# qfp160_socket_new.net
KiCad netlist of a schematic drawn in EAGLE
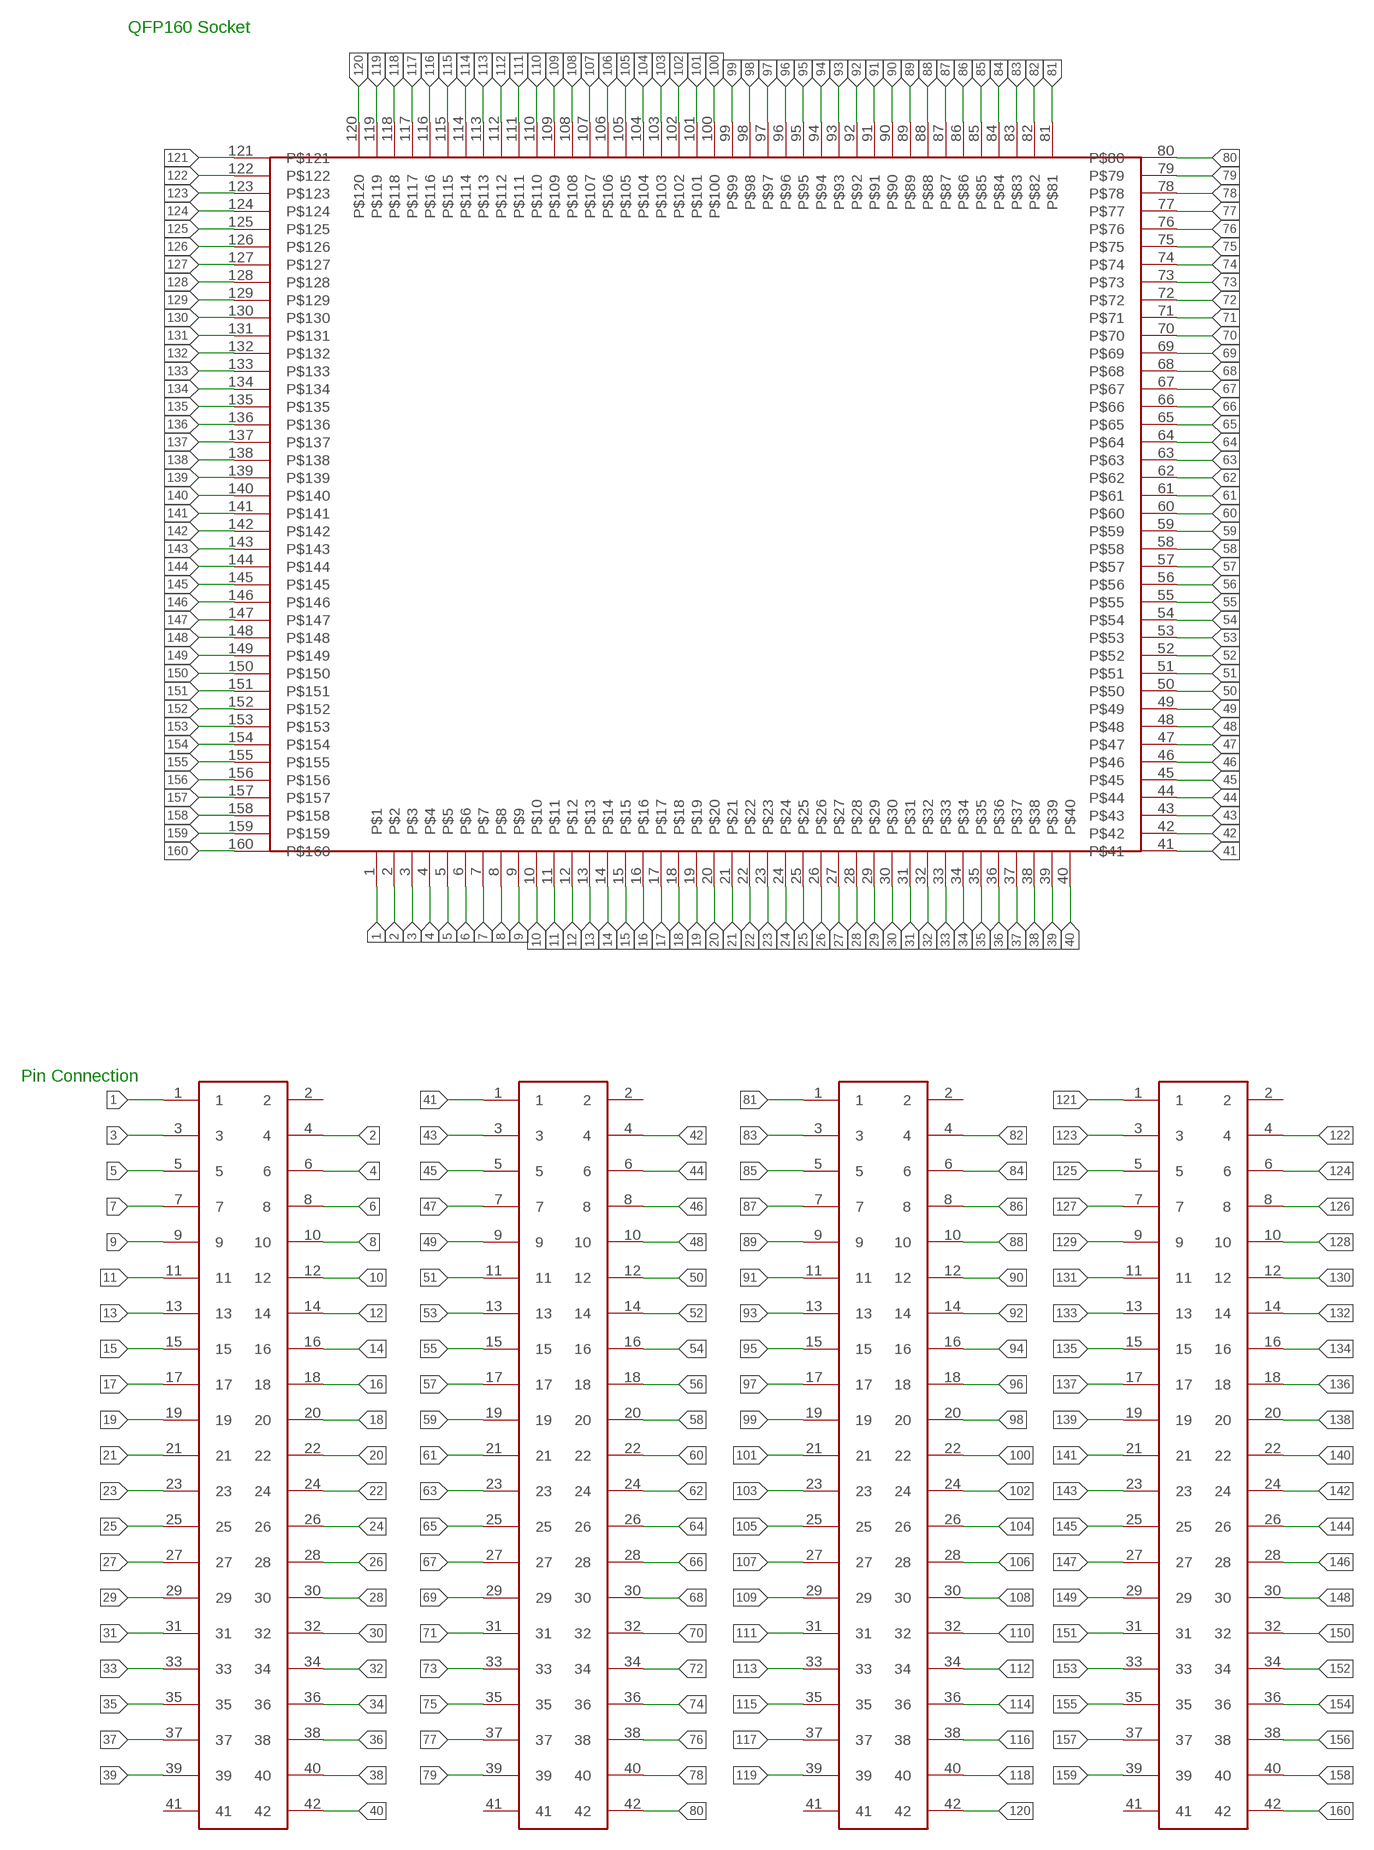
[diagram p0: schematic, sheet 1]

(export (version "E")
  (design (tool "Eeschema 10.0.6"))
  (components
    (comp (ref "U$1")
      (value "2X41_HEADER")
      (footprint "eagle-import:2X41_HEADER")
      (libsource (lib "eagle-import") (part "2X41_HEADER"))
    )
    (comp (ref "U$2")
      (value "2X41_HEADER")
      (footprint "eagle-import:2X41_HEADER")
      (libsource (lib "eagle-import") (part "2X41_HEADER"))
    )
    (comp (ref "U$3")
      (value "2X41_HEADER")
      (footprint "eagle-import:2X41_HEADER")
      (libsource (lib "eagle-import") (part "2X41_HEADER"))
    )
    (comp (ref "U$4")
      (value "2X41_HEADER")
      (footprint "eagle-import:2X41_HEADER")
      (libsource (lib "eagle-import") (part "2X41_HEADER"))
    )
    (comp (ref "U$5")
      (value "QFP160_SOCKET")
      (footprint "eagle-import:QFP160_SOCKET")
      (libsource (lib "eagle-import") (part "QFP160_SOCKET"))
    )
  )
  (nets
    (net (code "1") (name "1") (class "Default")
      (node (ref "U$1") (pin "1") (pinfunction "1_1") (pintype "bidirectional"))
      (node (ref "U$5") (pin "1") (pinfunction "P$1_1") (pintype "bidirectional"))
    )
    (net (code "2") (name "2") (class "Default")
      (node (ref "U$1") (pin "4") (pinfunction "4_4") (pintype "bidirectional"))
      (node (ref "U$5") (pin "2") (pinfunction "P$2_2") (pintype "bidirectional"))
    )
    (net (code "3") (name "3") (class "Default")
      (node (ref "U$1") (pin "3") (pinfunction "3_3") (pintype "bidirectional"))
      (node (ref "U$5") (pin "3") (pinfunction "P$3_3") (pintype "bidirectional"))
    )
    (net (code "4") (name "4") (class "Default")
      (node (ref "U$1") (pin "6") (pinfunction "6_6") (pintype "bidirectional"))
      (node (ref "U$5") (pin "4") (pinfunction "P$4_4") (pintype "bidirectional"))
    )
    (net (code "5") (name "5") (class "Default")
      (node (ref "U$1") (pin "5") (pinfunction "5_5") (pintype "bidirectional"))
      (node (ref "U$5") (pin "5") (pinfunction "P$5_5") (pintype "bidirectional"))
    )
    (net (code "6") (name "6") (class "Default")
      (node (ref "U$1") (pin "8") (pinfunction "8_8") (pintype "bidirectional"))
      (node (ref "U$5") (pin "6") (pinfunction "P$6_6") (pintype "bidirectional"))
    )
    (net (code "7") (name "7") (class "Default")
      (node (ref "U$1") (pin "7") (pinfunction "7_7") (pintype "bidirectional"))
      (node (ref "U$5") (pin "7") (pinfunction "P$7_7") (pintype "bidirectional"))
    )
    (net (code "8") (name "8") (class "Default")
      (node (ref "U$1") (pin "10") (pinfunction "10_10") (pintype "bidirectional"))
      (node (ref "U$5") (pin "8") (pinfunction "P$8_8") (pintype "bidirectional"))
    )
    (net (code "9") (name "9") (class "Default")
      (node (ref "U$1") (pin "9") (pinfunction "9_9") (pintype "bidirectional"))
      (node (ref "U$5") (pin "9") (pinfunction "P$9_9") (pintype "bidirectional"))
    )
    (net (code "10") (name "10") (class "Default")
      (node (ref "U$1") (pin "12") (pinfunction "12_12") (pintype "bidirectional"))
      (node (ref "U$5") (pin "10") (pinfunction "P$10_10") (pintype "bidirectional"))
    )
    (net (code "11") (name "11") (class "Default")
      (node (ref "U$1") (pin "11") (pinfunction "11_11") (pintype "bidirectional"))
      (node (ref "U$5") (pin "11") (pinfunction "P$11_11") (pintype "bidirectional"))
    )
    (net (code "12") (name "12") (class "Default")
      (node (ref "U$1") (pin "14") (pinfunction "14_14") (pintype "bidirectional"))
      (node (ref "U$5") (pin "12") (pinfunction "P$12_12") (pintype "bidirectional"))
    )
    (net (code "13") (name "13") (class "Default")
      (node (ref "U$1") (pin "13") (pinfunction "13_13") (pintype "bidirectional"))
      (node (ref "U$5") (pin "13") (pinfunction "P$13_13") (pintype "bidirectional"))
    )
    (net (code "14") (name "14") (class "Default")
      (node (ref "U$1") (pin "16") (pinfunction "16_16") (pintype "bidirectional"))
      (node (ref "U$5") (pin "14") (pinfunction "P$14_14") (pintype "bidirectional"))
    )
    (net (code "15") (name "15") (class "Default")
      (node (ref "U$1") (pin "15") (pinfunction "15_15") (pintype "bidirectional"))
      (node (ref "U$5") (pin "15") (pinfunction "P$15_15") (pintype "bidirectional"))
    )
    (net (code "16") (name "16") (class "Default")
      (node (ref "U$1") (pin "18") (pinfunction "18_18") (pintype "bidirectional"))
      (node (ref "U$5") (pin "16") (pinfunction "P$16_16") (pintype "bidirectional"))
    )
    (net (code "17") (name "17") (class "Default")
      (node (ref "U$1") (pin "17") (pinfunction "17_17") (pintype "bidirectional"))
      (node (ref "U$5") (pin "17") (pinfunction "P$17_17") (pintype "bidirectional"))
    )
    (net (code "18") (name "18") (class "Default")
      (node (ref "U$1") (pin "20") (pinfunction "20_20") (pintype "bidirectional"))
      (node (ref "U$5") (pin "18") (pinfunction "P$18_18") (pintype "bidirectional"))
    )
    (net (code "19") (name "19") (class "Default")
      (node (ref "U$1") (pin "19") (pinfunction "19_19") (pintype "bidirectional"))
      (node (ref "U$5") (pin "19") (pinfunction "P$19_19") (pintype "bidirectional"))
    )
    (net (code "20") (name "20") (class "Default")
      (node (ref "U$1") (pin "22") (pinfunction "22_22") (pintype "bidirectional"))
      (node (ref "U$5") (pin "20") (pinfunction "P$20_20") (pintype "bidirectional"))
    )
    (net (code "21") (name "21") (class "Default")
      (node (ref "U$1") (pin "21") (pinfunction "21_21") (pintype "bidirectional"))
      (node (ref "U$5") (pin "21") (pinfunction "P$21_21") (pintype "bidirectional"))
    )
    (net (code "22") (name "22") (class "Default")
      (node (ref "U$1") (pin "24") (pinfunction "24_24") (pintype "bidirectional"))
      (node (ref "U$5") (pin "22") (pinfunction "P$22_22") (pintype "bidirectional"))
    )
    (net (code "23") (name "23") (class "Default")
      (node (ref "U$1") (pin "23") (pinfunction "23_23") (pintype "bidirectional"))
      (node (ref "U$5") (pin "23") (pinfunction "P$23_23") (pintype "bidirectional"))
    )
    (net (code "24") (name "24") (class "Default")
      (node (ref "U$1") (pin "26") (pinfunction "26_26") (pintype "bidirectional"))
      (node (ref "U$5") (pin "24") (pinfunction "P$24_24") (pintype "bidirectional"))
    )
    (net (code "25") (name "25") (class "Default")
      (node (ref "U$1") (pin "25") (pinfunction "25_25") (pintype "bidirectional"))
      (node (ref "U$5") (pin "25") (pinfunction "P$25_25") (pintype "bidirectional"))
    )
    (net (code "26") (name "26") (class "Default")
      (node (ref "U$1") (pin "28") (pinfunction "28_28") (pintype "bidirectional"))
      (node (ref "U$5") (pin "26") (pinfunction "P$26_26") (pintype "bidirectional"))
    )
    (net (code "27") (name "27") (class "Default")
      (node (ref "U$1") (pin "27") (pinfunction "27_27") (pintype "bidirectional"))
      (node (ref "U$5") (pin "27") (pinfunction "P$27_27") (pintype "bidirectional"))
    )
    (net (code "28") (name "28") (class "Default")
      (node (ref "U$1") (pin "30") (pinfunction "30_30") (pintype "bidirectional"))
      (node (ref "U$5") (pin "28") (pinfunction "P$28_28") (pintype "bidirectional"))
    )
    (net (code "29") (name "29") (class "Default")
      (node (ref "U$1") (pin "29") (pinfunction "29_29") (pintype "bidirectional"))
      (node (ref "U$5") (pin "29") (pinfunction "P$29_29") (pintype "bidirectional"))
    )
    (net (code "30") (name "30") (class "Default")
      (node (ref "U$1") (pin "32") (pinfunction "32_32") (pintype "bidirectional"))
      (node (ref "U$5") (pin "30") (pinfunction "P$30_30") (pintype "bidirectional"))
    )
    (net (code "31") (name "31") (class "Default")
      (node (ref "U$1") (pin "31") (pinfunction "31_31") (pintype "bidirectional"))
      (node (ref "U$5") (pin "31") (pinfunction "P$31_31") (pintype "bidirectional"))
    )
    (net (code "32") (name "32") (class "Default")
      (node (ref "U$1") (pin "34") (pinfunction "34_34") (pintype "bidirectional"))
      (node (ref "U$5") (pin "32") (pinfunction "P$32_32") (pintype "bidirectional"))
    )
    (net (code "33") (name "33") (class "Default")
      (node (ref "U$1") (pin "33") (pinfunction "33_33") (pintype "bidirectional"))
      (node (ref "U$5") (pin "33") (pinfunction "P$33_33") (pintype "bidirectional"))
    )
    (net (code "34") (name "34") (class "Default")
      (node (ref "U$1") (pin "36") (pinfunction "36_36") (pintype "bidirectional"))
      (node (ref "U$5") (pin "34") (pinfunction "P$34_34") (pintype "bidirectional"))
    )
    (net (code "35") (name "35") (class "Default")
      (node (ref "U$1") (pin "35") (pinfunction "35_35") (pintype "bidirectional"))
      (node (ref "U$5") (pin "35") (pinfunction "P$35_35") (pintype "bidirectional"))
    )
    (net (code "36") (name "36") (class "Default")
      (node (ref "U$1") (pin "38") (pinfunction "38_38") (pintype "bidirectional"))
      (node (ref "U$5") (pin "36") (pinfunction "P$36_36") (pintype "bidirectional"))
    )
    (net (code "37") (name "37") (class "Default")
      (node (ref "U$1") (pin "37") (pinfunction "37_37") (pintype "bidirectional"))
      (node (ref "U$5") (pin "37") (pinfunction "P$37_37") (pintype "bidirectional"))
    )
    (net (code "38") (name "38") (class "Default")
      (node (ref "U$1") (pin "40") (pinfunction "40_40") (pintype "bidirectional"))
      (node (ref "U$5") (pin "38") (pinfunction "P$38_38") (pintype "bidirectional"))
    )
    (net (code "39") (name "39") (class "Default")
      (node (ref "U$1") (pin "39") (pinfunction "39_39") (pintype "bidirectional"))
      (node (ref "U$5") (pin "39") (pinfunction "P$39_39") (pintype "bidirectional"))
    )
    (net (code "40") (name "40") (class "Default")
      (node (ref "U$1") (pin "42") (pinfunction "42_42") (pintype "bidirectional"))
      (node (ref "U$5") (pin "40") (pinfunction "P$40_40") (pintype "bidirectional"))
    )
    (net (code "41") (name "41") (class "Default")
      (node (ref "U$2") (pin "1") (pinfunction "1_1") (pintype "bidirectional"))
      (node (ref "U$5") (pin "41") (pinfunction "P$41_41") (pintype "bidirectional"))
    )
    (net (code "42") (name "42") (class "Default")
      (node (ref "U$2") (pin "4") (pinfunction "4_4") (pintype "bidirectional"))
      (node (ref "U$5") (pin "42") (pinfunction "P$42_42") (pintype "bidirectional"))
    )
    (net (code "43") (name "43") (class "Default")
      (node (ref "U$2") (pin "3") (pinfunction "3_3") (pintype "bidirectional"))
      (node (ref "U$5") (pin "43") (pinfunction "P$43_43") (pintype "bidirectional"))
    )
    (net (code "44") (name "44") (class "Default")
      (node (ref "U$2") (pin "6") (pinfunction "6_6") (pintype "bidirectional"))
      (node (ref "U$5") (pin "44") (pinfunction "P$44_44") (pintype "bidirectional"))
    )
    (net (code "45") (name "45") (class "Default")
      (node (ref "U$2") (pin "5") (pinfunction "5_5") (pintype "bidirectional"))
      (node (ref "U$5") (pin "45") (pinfunction "P$45_45") (pintype "bidirectional"))
    )
    (net (code "46") (name "46") (class "Default")
      (node (ref "U$2") (pin "8") (pinfunction "8_8") (pintype "bidirectional"))
      (node (ref "U$5") (pin "46") (pinfunction "P$46_46") (pintype "bidirectional"))
    )
    (net (code "47") (name "47") (class "Default")
      (node (ref "U$2") (pin "7") (pinfunction "7_7") (pintype "bidirectional"))
      (node (ref "U$5") (pin "47") (pinfunction "P$47_47") (pintype "bidirectional"))
    )
    (net (code "48") (name "48") (class "Default")
      (node (ref "U$2") (pin "10") (pinfunction "10_10") (pintype "bidirectional"))
      (node (ref "U$5") (pin "48") (pinfunction "P$48_48") (pintype "bidirectional"))
    )
    (net (code "49") (name "49") (class "Default")
      (node (ref "U$2") (pin "9") (pinfunction "9_9") (pintype "bidirectional"))
      (node (ref "U$5") (pin "49") (pinfunction "P$49_49") (pintype "bidirectional"))
    )
    (net (code "50") (name "50") (class "Default")
      (node (ref "U$2") (pin "12") (pinfunction "12_12") (pintype "bidirectional"))
      (node (ref "U$5") (pin "50") (pinfunction "P$50_50") (pintype "bidirectional"))
    )
    (net (code "51") (name "51") (class "Default")
      (node (ref "U$2") (pin "11") (pinfunction "11_11") (pintype "bidirectional"))
      (node (ref "U$5") (pin "51") (pinfunction "P$51_51") (pintype "bidirectional"))
    )
    (net (code "52") (name "52") (class "Default")
      (node (ref "U$2") (pin "14") (pinfunction "14_14") (pintype "bidirectional"))
      (node (ref "U$5") (pin "52") (pinfunction "P$52_52") (pintype "bidirectional"))
    )
    (net (code "53") (name "53") (class "Default")
      (node (ref "U$2") (pin "13") (pinfunction "13_13") (pintype "bidirectional"))
      (node (ref "U$5") (pin "53") (pinfunction "P$53_53") (pintype "bidirectional"))
    )
    (net (code "54") (name "54") (class "Default")
      (node (ref "U$2") (pin "16") (pinfunction "16_16") (pintype "bidirectional"))
      (node (ref "U$5") (pin "54") (pinfunction "P$54_54") (pintype "bidirectional"))
    )
    (net (code "55") (name "55") (class "Default")
      (node (ref "U$2") (pin "15") (pinfunction "15_15") (pintype "bidirectional"))
      (node (ref "U$5") (pin "55") (pinfunction "P$55_55") (pintype "bidirectional"))
    )
    (net (code "56") (name "56") (class "Default")
      (node (ref "U$2") (pin "18") (pinfunction "18_18") (pintype "bidirectional"))
      (node (ref "U$5") (pin "56") (pinfunction "P$56_56") (pintype "bidirectional"))
    )
    (net (code "57") (name "57") (class "Default")
      (node (ref "U$2") (pin "17") (pinfunction "17_17") (pintype "bidirectional"))
      (node (ref "U$5") (pin "57") (pinfunction "P$57_57") (pintype "bidirectional"))
    )
    (net (code "58") (name "58") (class "Default")
      (node (ref "U$2") (pin "20") (pinfunction "20_20") (pintype "bidirectional"))
      (node (ref "U$5") (pin "58") (pinfunction "P$58_58") (pintype "bidirectional"))
    )
    (net (code "59") (name "59") (class "Default")
      (node (ref "U$2") (pin "19") (pinfunction "19_19") (pintype "bidirectional"))
      (node (ref "U$5") (pin "59") (pinfunction "P$59_59") (pintype "bidirectional"))
    )
    (net (code "60") (name "60") (class "Default")
      (node (ref "U$2") (pin "22") (pinfunction "22_22") (pintype "bidirectional"))
      (node (ref "U$5") (pin "60") (pinfunction "P$60_60") (pintype "bidirectional"))
    )
    (net (code "61") (name "61") (class "Default")
      (node (ref "U$2") (pin "21") (pinfunction "21_21") (pintype "bidirectional"))
      (node (ref "U$5") (pin "61") (pinfunction "P$61_61") (pintype "bidirectional"))
    )
    (net (code "62") (name "62") (class "Default")
      (node (ref "U$2") (pin "24") (pinfunction "24_24") (pintype "bidirectional"))
      (node (ref "U$5") (pin "62") (pinfunction "P$62_62") (pintype "bidirectional"))
    )
    (net (code "63") (name "63") (class "Default")
      (node (ref "U$2") (pin "23") (pinfunction "23_23") (pintype "bidirectional"))
      (node (ref "U$5") (pin "63") (pinfunction "P$63_63") (pintype "bidirectional"))
    )
    (net (code "64") (name "64") (class "Default")
      (node (ref "U$2") (pin "26") (pinfunction "26_26") (pintype "bidirectional"))
      (node (ref "U$5") (pin "64") (pinfunction "P$64_64") (pintype "bidirectional"))
    )
    (net (code "65") (name "65") (class "Default")
      (node (ref "U$2") (pin "25") (pinfunction "25_25") (pintype "bidirectional"))
      (node (ref "U$5") (pin "65") (pinfunction "P$65_65") (pintype "bidirectional"))
    )
    (net (code "66") (name "66") (class "Default")
      (node (ref "U$2") (pin "28") (pinfunction "28_28") (pintype "bidirectional"))
      (node (ref "U$5") (pin "66") (pinfunction "P$66_66") (pintype "bidirectional"))
    )
    (net (code "67") (name "67") (class "Default")
      (node (ref "U$2") (pin "27") (pinfunction "27_27") (pintype "bidirectional"))
      (node (ref "U$5") (pin "67") (pinfunction "P$67_67") (pintype "bidirectional"))
    )
    (net (code "68") (name "68") (class "Default")
      (node (ref "U$2") (pin "30") (pinfunction "30_30") (pintype "bidirectional"))
      (node (ref "U$5") (pin "68") (pinfunction "P$68_68") (pintype "bidirectional"))
    )
    (net (code "69") (name "69") (class "Default")
      (node (ref "U$2") (pin "29") (pinfunction "29_29") (pintype "bidirectional"))
      (node (ref "U$5") (pin "69") (pinfunction "P$69_69") (pintype "bidirectional"))
    )
    (net (code "70") (name "70") (class "Default")
      (node (ref "U$2") (pin "32") (pinfunction "32_32") (pintype "bidirectional"))
      (node (ref "U$5") (pin "70") (pinfunction "P$70_70") (pintype "bidirectional"))
    )
    (net (code "71") (name "71") (class "Default")
      (node (ref "U$2") (pin "31") (pinfunction "31_31") (pintype "bidirectional"))
      (node (ref "U$5") (pin "71") (pinfunction "P$71_71") (pintype "bidirectional"))
    )
    (net (code "72") (name "72") (class "Default")
      (node (ref "U$2") (pin "34") (pinfunction "34_34") (pintype "bidirectional"))
      (node (ref "U$5") (pin "72") (pinfunction "P$72_72") (pintype "bidirectional"))
    )
    (net (code "73") (name "73") (class "Default")
      (node (ref "U$2") (pin "33") (pinfunction "33_33") (pintype "bidirectional"))
      (node (ref "U$5") (pin "73") (pinfunction "P$73_73") (pintype "bidirectional"))
    )
    (net (code "74") (name "74") (class "Default")
      (node (ref "U$2") (pin "36") (pinfunction "36_36") (pintype "bidirectional"))
      (node (ref "U$5") (pin "74") (pinfunction "P$74_74") (pintype "bidirectional"))
    )
    (net (code "75") (name "75") (class "Default")
      (node (ref "U$2") (pin "35") (pinfunction "35_35") (pintype "bidirectional"))
      (node (ref "U$5") (pin "75") (pinfunction "P$75_75") (pintype "bidirectional"))
    )
    (net (code "76") (name "76") (class "Default")
      (node (ref "U$2") (pin "38") (pinfunction "38_38") (pintype "bidirectional"))
      (node (ref "U$5") (pin "76") (pinfunction "P$76_76") (pintype "bidirectional"))
    )
    (net (code "77") (name "77") (class "Default")
      (node (ref "U$2") (pin "37") (pinfunction "37_37") (pintype "bidirectional"))
      (node (ref "U$5") (pin "77") (pinfunction "P$77_77") (pintype "bidirectional"))
    )
    (net (code "78") (name "78") (class "Default")
      (node (ref "U$2") (pin "40") (pinfunction "40_40") (pintype "bidirectional"))
      (node (ref "U$5") (pin "78") (pinfunction "P$78_78") (pintype "bidirectional"))
    )
    (net (code "79") (name "79") (class "Default")
      (node (ref "U$2") (pin "39") (pinfunction "39_39") (pintype "bidirectional"))
      (node (ref "U$5") (pin "79") (pinfunction "P$79_79") (pintype "bidirectional"))
    )
    (net (code "80") (name "80") (class "Default")
      (node (ref "U$2") (pin "42") (pinfunction "42_42") (pintype "bidirectional"))
      (node (ref "U$5") (pin "80") (pinfunction "P$80_80") (pintype "bidirectional"))
    )
    (net (code "81") (name "81") (class "Default")
      (node (ref "U$3") (pin "1") (pinfunction "1_1") (pintype "bidirectional"))
      (node (ref "U$5") (pin "81") (pinfunction "P$81_81") (pintype "bidirectional"))
    )
    (net (code "82") (name "82") (class "Default")
      (node (ref "U$3") (pin "4") (pinfunction "4_4") (pintype "bidirectional"))
      (node (ref "U$5") (pin "82") (pinfunction "P$82_82") (pintype "bidirectional"))
    )
    (net (code "83") (name "83") (class "Default")
      (node (ref "U$3") (pin "3") (pinfunction "3_3") (pintype "bidirectional"))
      (node (ref "U$5") (pin "83") (pinfunction "P$83_83") (pintype "bidirectional"))
    )
    (net (code "84") (name "84") (class "Default")
      (node (ref "U$3") (pin "6") (pinfunction "6_6") (pintype "bidirectional"))
      (node (ref "U$5") (pin "84") (pinfunction "P$84_84") (pintype "bidirectional"))
    )
    (net (code "85") (name "85") (class "Default")
      (node (ref "U$3") (pin "5") (pinfunction "5_5") (pintype "bidirectional"))
      (node (ref "U$5") (pin "85") (pinfunction "P$85_85") (pintype "bidirectional"))
    )
    (net (code "86") (name "86") (class "Default")
      (node (ref "U$3") (pin "8") (pinfunction "8_8") (pintype "bidirectional"))
      (node (ref "U$5") (pin "86") (pinfunction "P$86_86") (pintype "bidirectional"))
    )
    (net (code "87") (name "87") (class "Default")
      (node (ref "U$3") (pin "7") (pinfunction "7_7") (pintype "bidirectional"))
      (node (ref "U$5") (pin "87") (pinfunction "P$87_87") (pintype "bidirectional"))
    )
    (net (code "88") (name "88") (class "Default")
      (node (ref "U$3") (pin "10") (pinfunction "10_10") (pintype "bidirectional"))
      (node (ref "U$5") (pin "88") (pinfunction "P$88_88") (pintype "bidirectional"))
    )
    (net (code "89") (name "89") (class "Default")
      (node (ref "U$3") (pin "9") (pinfunction "9_9") (pintype "bidirectional"))
      (node (ref "U$5") (pin "89") (pinfunction "P$89_89") (pintype "bidirectional"))
    )
    (net (code "90") (name "90") (class "Default")
      (node (ref "U$3") (pin "12") (pinfunction "12_12") (pintype "bidirectional"))
      (node (ref "U$5") (pin "90") (pinfunction "P$90_90") (pintype "bidirectional"))
    )
    (net (code "91") (name "91") (class "Default")
      (node (ref "U$3") (pin "11") (pinfunction "11_11") (pintype "bidirectional"))
      (node (ref "U$5") (pin "91") (pinfunction "P$91_91") (pintype "bidirectional"))
    )
    (net (code "92") (name "92") (class "Default")
      (node (ref "U$3") (pin "14") (pinfunction "14_14") (pintype "bidirectional"))
      (node (ref "U$5") (pin "92") (pinfunction "P$92_92") (pintype "bidirectional"))
    )
    (net (code "93") (name "93") (class "Default")
      (node (ref "U$3") (pin "13") (pinfunction "13_13") (pintype "bidirectional"))
      (node (ref "U$5") (pin "93") (pinfunction "P$93_93") (pintype "bidirectional"))
    )
    (net (code "94") (name "94") (class "Default")
      (node (ref "U$3") (pin "16") (pinfunction "16_16") (pintype "bidirectional"))
      (node (ref "U$5") (pin "94") (pinfunction "P$94_94") (pintype "bidirectional"))
    )
    (net (code "95") (name "95") (class "Default")
      (node (ref "U$3") (pin "15") (pinfunction "15_15") (pintype "bidirectional"))
      (node (ref "U$5") (pin "95") (pinfunction "P$95_95") (pintype "bidirectional"))
    )
    (net (code "96") (name "96") (class "Default")
      (node (ref "U$3") (pin "18") (pinfunction "18_18") (pintype "bidirectional"))
      (node (ref "U$5") (pin "96") (pinfunction "P$96_96") (pintype "bidirectional"))
    )
    (net (code "97") (name "97") (class "Default")
      (node (ref "U$3") (pin "17") (pinfunction "17_17") (pintype "bidirectional"))
      (node (ref "U$5") (pin "97") (pinfunction "P$97_97") (pintype "bidirectional"))
    )
    (net (code "98") (name "98") (class "Default")
      (node (ref "U$3") (pin "20") (pinfunction "20_20") (pintype "bidirectional"))
      (node (ref "U$5") (pin "98") (pinfunction "P$98_98") (pintype "bidirectional"))
    )
    (net (code "99") (name "99") (class "Default")
      (node (ref "U$3") (pin "19") (pinfunction "19_19") (pintype "bidirectional"))
      (node (ref "U$5") (pin "99") (pinfunction "P$99_99") (pintype "bidirectional"))
    )
    (net (code "100") (name "100") (class "Default")
      (node (ref "U$3") (pin "22") (pinfunction "22_22") (pintype "bidirectional"))
      (node (ref "U$5") (pin "100") (pinfunction "P$100_100") (pintype "bidirectional"))
    )
    (net (code "101") (name "101") (class "Default")
      (node (ref "U$3") (pin "21") (pinfunction "21_21") (pintype "bidirectional"))
      (node (ref "U$5") (pin "101") (pinfunction "P$101_101") (pintype "bidirectional"))
    )
    (net (code "102") (name "102") (class "Default")
      (node (ref "U$3") (pin "24") (pinfunction "24_24") (pintype "bidirectional"))
      (node (ref "U$5") (pin "102") (pinfunction "P$102_102") (pintype "bidirectional"))
    )
    (net (code "103") (name "103") (class "Default")
      (node (ref "U$3") (pin "23") (pinfunction "23_23") (pintype "bidirectional"))
      (node (ref "U$5") (pin "103") (pinfunction "P$103_103") (pintype "bidirectional"))
    )
    (net (code "104") (name "104") (class "Default")
      (node (ref "U$3") (pin "26") (pinfunction "26_26") (pintype "bidirectional"))
      (node (ref "U$5") (pin "104") (pinfunction "P$104_104") (pintype "bidirectional"))
    )
    (net (code "105") (name "105") (class "Default")
      (node (ref "U$3") (pin "25") (pinfunction "25_25") (pintype "bidirectional"))
      (node (ref "U$5") (pin "105") (pinfunction "P$105_105") (pintype "bidirectional"))
    )
    (net (code "106") (name "106") (class "Default")
      (node (ref "U$3") (pin "28") (pinfunction "28_28") (pintype "bidirectional"))
      (node (ref "U$5") (pin "106") (pinfunction "P$106_106") (pintype "bidirectional"))
    )
    (net (code "107") (name "107") (class "Default")
      (node (ref "U$3") (pin "27") (pinfunction "27_27") (pintype "bidirectional"))
      (node (ref "U$5") (pin "107") (pinfunction "P$107_107") (pintype "bidirectional"))
    )
    (net (code "108") (name "108") (class "Default")
      (node (ref "U$3") (pin "30") (pinfunction "30_30") (pintype "bidirectional"))
      (node (ref "U$5") (pin "108") (pinfunction "P$108_108") (pintype "bidirectional"))
    )
    (net (code "109") (name "109") (class "Default")
      (node (ref "U$3") (pin "29") (pinfunction "29_29") (pintype "bidirectional"))
      (node (ref "U$5") (pin "109") (pinfunction "P$109_109") (pintype "bidirectional"))
    )
    (net (code "110") (name "110") (class "Default")
      (node (ref "U$3") (pin "32") (pinfunction "32_32") (pintype "bidirectional"))
      (node (ref "U$5") (pin "110") (pinfunction "P$110_110") (pintype "bidirectional"))
    )
    (net (code "111") (name "111") (class "Default")
      (node (ref "U$3") (pin "31") (pinfunction "31_31") (pintype "bidirectional"))
      (node (ref "U$5") (pin "111") (pinfunction "P$111_111") (pintype "bidirectional"))
    )
    (net (code "112") (name "112") (class "Default")
      (node (ref "U$3") (pin "34") (pinfunction "34_34") (pintype "bidirectional"))
      (node (ref "U$5") (pin "112") (pinfunction "P$112_112") (pintype "bidirectional"))
    )
    (net (code "113") (name "113") (class "Default")
      (node (ref "U$3") (pin "33") (pinfunction "33_33") (pintype "bidirectional"))
      (node (ref "U$5") (pin "113") (pinfunction "P$113_113") (pintype "bidirectional"))
    )
    (net (code "114") (name "114") (class "Default")
      (node (ref "U$3") (pin "36") (pinfunction "36_36") (pintype "bidirectional"))
      (node (ref "U$5") (pin "114") (pinfunction "P$114_114") (pintype "bidirectional"))
    )
    (net (code "115") (name "115") (class "Default")
      (node (ref "U$3") (pin "35") (pinfunction "35_35") (pintype "bidirectional"))
      (node (ref "U$5") (pin "115") (pinfunction "P$115_115") (pintype "bidirectional"))
    )
    (net (code "116") (name "116") (class "Default")
      (node (ref "U$3") (pin "38") (pinfunction "38_38") (pintype "bidirectional"))
      (node (ref "U$5") (pin "116") (pinfunction "P$116_116") (pintype "bidirectional"))
    )
    (net (code "117") (name "117") (class "Default")
      (node (ref "U$3") (pin "37") (pinfunction "37_37") (pintype "bidirectional"))
      (node (ref "U$5") (pin "117") (pinfunction "P$117_117") (pintype "bidirectional"))
    )
    (net (code "118") (name "118") (class "Default")
      (node (ref "U$3") (pin "40") (pinfunction "40_40") (pintype "bidirectional"))
      (node (ref "U$5") (pin "118") (pinfunction "P$118_118") (pintype "bidirectional"))
    )
    (net (code "119") (name "119") (class "Default")
      (node (ref "U$3") (pin "39") (pinfunction "39_39") (pintype "bidirectional"))
      (node (ref "U$5") (pin "119") (pinfunction "P$119_119") (pintype "bidirectional"))
    )
    (net (code "120") (name "120") (class "Default")
      (node (ref "U$3") (pin "42") (pinfunction "42_42") (pintype "bidirectional"))
      (node (ref "U$5") (pin "120") (pinfunction "P$120_120") (pintype "bidirectional"))
    )
    (net (code "121") (name "121") (class "Default")
      (node (ref "U$4") (pin "1") (pinfunction "1_1") (pintype "bidirectional"))
      (node (ref "U$5") (pin "121") (pinfunction "P$121_121") (pintype "bidirectional"))
    )
    (net (code "122") (name "122") (class "Default")
      (node (ref "U$4") (pin "4") (pinfunction "4_4") (pintype "bidirectional"))
      (node (ref "U$5") (pin "122") (pinfunction "P$122_122") (pintype "bidirectional"))
    )
    (net (code "123") (name "123") (class "Default")
      (node (ref "U$4") (pin "3") (pinfunction "3_3") (pintype "bidirectional"))
      (node (ref "U$5") (pin "123") (pinfunction "P$123_123") (pintype "bidirectional"))
    )
    (net (code "124") (name "124") (class "Default")
      (node (ref "U$4") (pin "6") (pinfunction "6_6") (pintype "bidirectional"))
      (node (ref "U$5") (pin "124") (pinfunction "P$124_124") (pintype "bidirectional"))
    )
    (net (code "125") (name "125") (class "Default")
      (node (ref "U$4") (pin "5") (pinfunction "5_5") (pintype "bidirectional"))
      (node (ref "U$5") (pin "125") (pinfunction "P$125_125") (pintype "bidirectional"))
    )
    (net (code "126") (name "126") (class "Default")
      (node (ref "U$4") (pin "8") (pinfunction "8_8") (pintype "bidirectional"))
      (node (ref "U$5") (pin "126") (pinfunction "P$126_126") (pintype "bidirectional"))
    )
    (net (code "127") (name "127") (class "Default")
      (node (ref "U$4") (pin "7") (pinfunction "7_7") (pintype "bidirectional"))
      (node (ref "U$5") (pin "127") (pinfunction "P$127_127") (pintype "bidirectional"))
    )
    (net (code "128") (name "128") (class "Default")
      (node (ref "U$4") (pin "10") (pinfunction "10_10") (pintype "bidirectional"))
      (node (ref "U$5") (pin "128") (pinfunction "P$128_128") (pintype "bidirectional"))
    )
    (net (code "129") (name "129") (class "Default")
      (node (ref "U$4") (pin "9") (pinfunction "9_9") (pintype "bidirectional"))
      (node (ref "U$5") (pin "129") (pinfunction "P$129_129") (pintype "bidirectional"))
    )
    (net (code "130") (name "130") (class "Default")
      (node (ref "U$4") (pin "12") (pinfunction "12_12") (pintype "bidirectional"))
      (node (ref "U$5") (pin "130") (pinfunction "P$130_130") (pintype "bidirectional"))
    )
    (net (code "131") (name "131") (class "Default")
      (node (ref "U$4") (pin "11") (pinfunction "11_11") (pintype "bidirectional"))
      (node (ref "U$5") (pin "131") (pinfunction "P$131_131") (pintype "bidirectional"))
    )
    (net (code "132") (name "132") (class "Default")
      (node (ref "U$4") (pin "14") (pinfunction "14_14") (pintype "bidirectional"))
      (node (ref "U$5") (pin "132") (pinfunction "P$132_132") (pintype "bidirectional"))
    )
    (net (code "133") (name "133") (class "Default")
      (node (ref "U$4") (pin "13") (pinfunction "13_13") (pintype "bidirectional"))
      (node (ref "U$5") (pin "133") (pinfunction "P$133_133") (pintype "bidirectional"))
    )
    (net (code "134") (name "134") (class "Default")
      (node (ref "U$4") (pin "16") (pinfunction "16_16") (pintype "bidirectional"))
      (node (ref "U$5") (pin "134") (pinfunction "P$134_134") (pintype "bidirectional"))
    )
    (net (code "135") (name "135") (class "Default")
      (node (ref "U$4") (pin "15") (pinfunction "15_15") (pintype "bidirectional"))
      (node (ref "U$5") (pin "135") (pinfunction "P$135_135") (pintype "bidirectional"))
    )
    (net (code "136") (name "136") (class "Default")
      (node (ref "U$4") (pin "18") (pinfunction "18_18") (pintype "bidirectional"))
      (node (ref "U$5") (pin "136") (pinfunction "P$136_136") (pintype "bidirectional"))
    )
    (net (code "137") (name "137") (class "Default")
      (node (ref "U$4") (pin "17") (pinfunction "17_17") (pintype "bidirectional"))
      (node (ref "U$5") (pin "137") (pinfunction "P$137_137") (pintype "bidirectional"))
    )
    (net (code "138") (name "138") (class "Default")
      (node (ref "U$4") (pin "20") (pinfunction "20_20") (pintype "bidirectional"))
      (node (ref "U$5") (pin "138") (pinfunction "P$138_138") (pintype "bidirectional"))
    )
    (net (code "139") (name "139") (class "Default")
      (node (ref "U$4") (pin "19") (pinfunction "19_19") (pintype "bidirectional"))
      (node (ref "U$5") (pin "139") (pinfunction "P$139_139") (pintype "bidirectional"))
    )
    (net (code "140") (name "140") (class "Default")
      (node (ref "U$4") (pin "22") (pinfunction "22_22") (pintype "bidirectional"))
      (node (ref "U$5") (pin "140") (pinfunction "P$140_140") (pintype "bidirectional"))
    )
    (net (code "141") (name "141") (class "Default")
      (node (ref "U$4") (pin "21") (pinfunction "21_21") (pintype "bidirectional"))
      (node (ref "U$5") (pin "141") (pinfunction "P$141_141") (pintype "bidirectional"))
    )
    (net (code "142") (name "142") (class "Default")
      (node (ref "U$4") (pin "24") (pinfunction "24_24") (pintype "bidirectional"))
      (node (ref "U$5") (pin "142") (pinfunction "P$142_142") (pintype "bidirectional"))
    )
    (net (code "143") (name "143") (class "Default")
      (node (ref "U$4") (pin "23") (pinfunction "23_23") (pintype "bidirectional"))
      (node (ref "U$5") (pin "143") (pinfunction "P$143_143") (pintype "bidirectional"))
    )
    (net (code "144") (name "144") (class "Default")
      (node (ref "U$4") (pin "26") (pinfunction "26_26") (pintype "bidirectional"))
      (node (ref "U$5") (pin "144") (pinfunction "P$144_144") (pintype "bidirectional"))
    )
    (net (code "145") (name "145") (class "Default")
      (node (ref "U$4") (pin "25") (pinfunction "25_25") (pintype "bidirectional"))
      (node (ref "U$5") (pin "145") (pinfunction "P$145_145") (pintype "bidirectional"))
    )
    (net (code "146") (name "146") (class "Default")
      (node (ref "U$4") (pin "28") (pinfunction "28_28") (pintype "bidirectional"))
      (node (ref "U$5") (pin "146") (pinfunction "P$146_146") (pintype "bidirectional"))
    )
    (net (code "147") (name "147") (class "Default")
      (node (ref "U$4") (pin "27") (pinfunction "27_27") (pintype "bidirectional"))
      (node (ref "U$5") (pin "147") (pinfunction "P$147_147") (pintype "bidirectional"))
    )
    (net (code "148") (name "148") (class "Default")
      (node (ref "U$4") (pin "30") (pinfunction "30_30") (pintype "bidirectional"))
      (node (ref "U$5") (pin "148") (pinfunction "P$148_148") (pintype "bidirectional"))
    )
    (net (code "149") (name "149") (class "Default")
      (node (ref "U$4") (pin "29") (pinfunction "29_29") (pintype "bidirectional"))
      (node (ref "U$5") (pin "149") (pinfunction "P$149_149") (pintype "bidirectional"))
    )
    (net (code "150") (name "150") (class "Default")
      (node (ref "U$4") (pin "32") (pinfunction "32_32") (pintype "bidirectional"))
      (node (ref "U$5") (pin "150") (pinfunction "P$150_150") (pintype "bidirectional"))
    )
    (net (code "151") (name "151") (class "Default")
      (node (ref "U$4") (pin "31") (pinfunction "31_31") (pintype "bidirectional"))
      (node (ref "U$5") (pin "151") (pinfunction "P$151_151") (pintype "bidirectional"))
    )
    (net (code "152") (name "152") (class "Default")
      (node (ref "U$4") (pin "34") (pinfunction "34_34") (pintype "bidirectional"))
      (node (ref "U$5") (pin "152") (pinfunction "P$152_152") (pintype "bidirectional"))
    )
    (net (code "153") (name "153") (class "Default")
      (node (ref "U$4") (pin "33") (pinfunction "33_33") (pintype "bidirectional"))
      (node (ref "U$5") (pin "153") (pinfunction "P$153_153") (pintype "bidirectional"))
    )
    (net (code "154") (name "154") (class "Default")
      (node (ref "U$4") (pin "36") (pinfunction "36_36") (pintype "bidirectional"))
      (node (ref "U$5") (pin "154") (pinfunction "P$154_154") (pintype "bidirectional"))
    )
    (net (code "155") (name "155") (class "Default")
      (node (ref "U$4") (pin "35") (pinfunction "35_35") (pintype "bidirectional"))
      (node (ref "U$5") (pin "155") (pinfunction "P$155_155") (pintype "bidirectional"))
    )
    (net (code "156") (name "156") (class "Default")
      (node (ref "U$4") (pin "38") (pinfunction "38_38") (pintype "bidirectional"))
      (node (ref "U$5") (pin "156") (pinfunction "P$156_156") (pintype "bidirectional"))
    )
    (net (code "157") (name "157") (class "Default")
      (node (ref "U$4") (pin "37") (pinfunction "37_37") (pintype "bidirectional"))
      (node (ref "U$5") (pin "157") (pinfunction "P$157_157") (pintype "bidirectional"))
    )
    (net (code "158") (name "158") (class "Default")
      (node (ref "U$4") (pin "40") (pinfunction "40_40") (pintype "bidirectional"))
      (node (ref "U$5") (pin "158") (pinfunction "P$158_158") (pintype "bidirectional"))
    )
    (net (code "159") (name "159") (class "Default")
      (node (ref "U$4") (pin "39") (pinfunction "39_39") (pintype "bidirectional"))
      (node (ref "U$5") (pin "159") (pinfunction "P$159_159") (pintype "bidirectional"))
    )
    (net (code "160") (name "160") (class "Default")
      (node (ref "U$4") (pin "42") (pinfunction "42_42") (pintype "bidirectional"))
      (node (ref "U$5") (pin "160") (pinfunction "P$160_160") (pintype "bidirectional"))
    )
    (net (code "161") (name "unconnected-(U$1-Pad2)") (class "Default")
      (node (ref "U$1") (pin "2") (pinfunction "2_2") (pintype "bidirectional"))
    )
    (net (code "162") (name "unconnected-(U$1-Pad41)") (class "Default")
      (node (ref "U$1") (pin "41") (pinfunction "41_41") (pintype "bidirectional"))
    )
    (net (code "163") (name "unconnected-(U$2-Pad2)") (class "Default")
      (node (ref "U$2") (pin "2") (pinfunction "2_2") (pintype "bidirectional"))
    )
    (net (code "164") (name "unconnected-(U$2-Pad41)") (class "Default")
      (node (ref "U$2") (pin "41") (pinfunction "41_41") (pintype "bidirectional"))
    )
    (net (code "165") (name "unconnected-(U$3-Pad2)") (class "Default")
      (node (ref "U$3") (pin "2") (pinfunction "2_2") (pintype "bidirectional"))
    )
    (net (code "166") (name "unconnected-(U$3-Pad41)") (class "Default")
      (node (ref "U$3") (pin "41") (pinfunction "41_41") (pintype "bidirectional"))
    )
    (net (code "167") (name "unconnected-(U$4-Pad2)") (class "Default")
      (node (ref "U$4") (pin "2") (pinfunction "2_2") (pintype "bidirectional"))
    )
    (net (code "168") (name "unconnected-(U$4-Pad41)") (class "Default")
      (node (ref "U$4") (pin "41") (pinfunction "41_41") (pintype "bidirectional"))
    )
  )
)
